# MainBoard.net
KiCad netlist of a schematic drawn in EAGLE
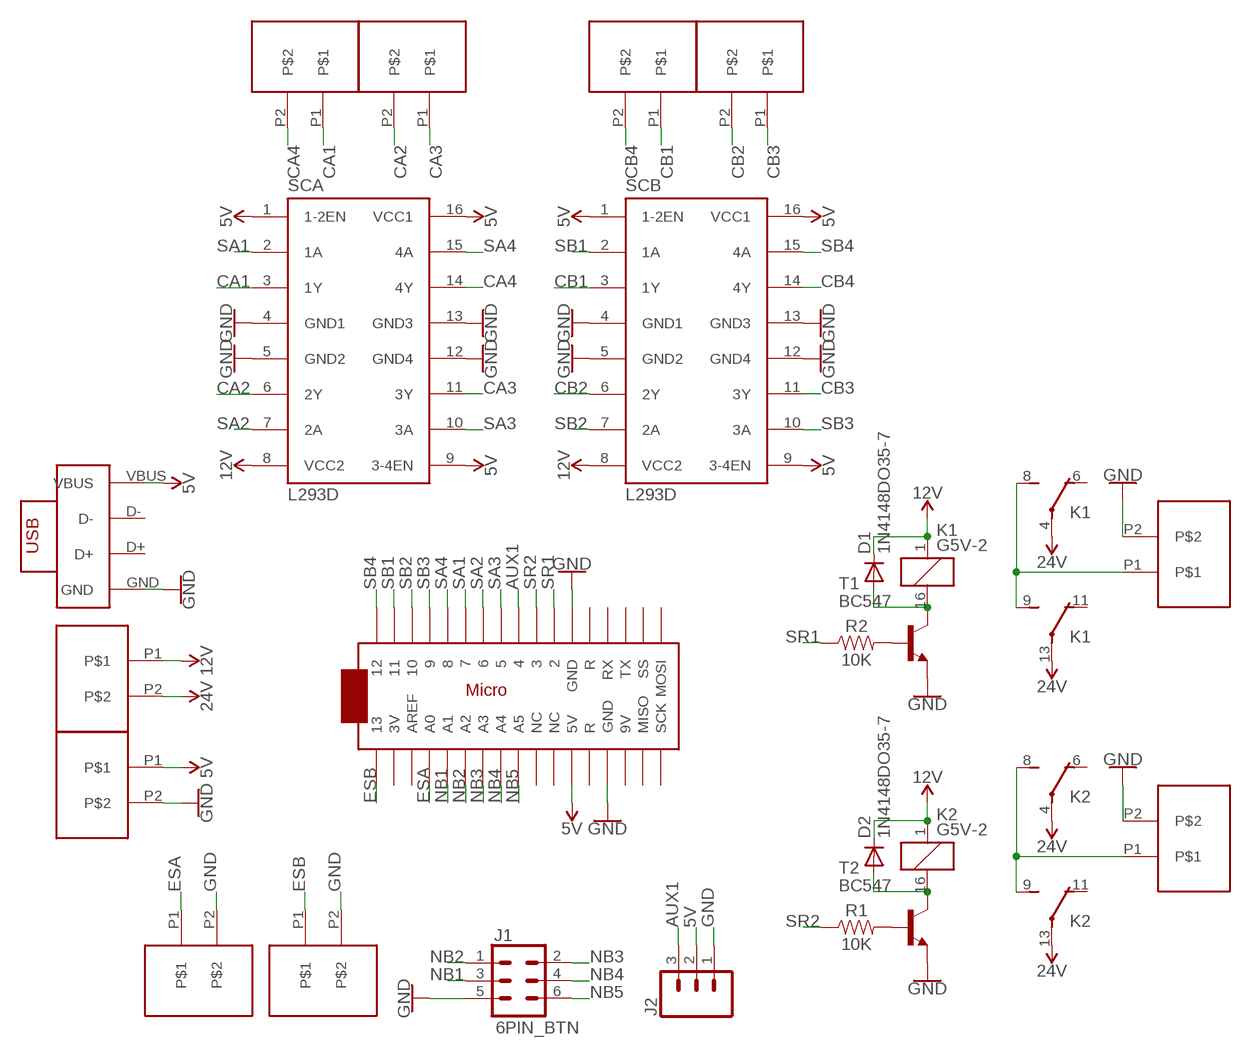
[diagram p0: schematic, sheet 1]

(export (version "E")
  (design (tool "Eeschema 10.0.6"))
  (components
    (comp (ref "5V/GND")
      (value "PRT-08432")
      (footprint "eagle-import:PRT-08432")
      (libsource (lib "eagle-import") (part "PRT-08432"))
    )
    (comp (ref "12/24V")
      (value "PRT-08432")
      (footprint "eagle-import:PRT-08432")
      (libsource (lib "eagle-import") (part "PRT-08432"))
    )
    (comp (ref "D1")
      (value "1N4148DO35-7")
      (footprint "eagle-import:DO35-7")
      (libsource (lib "eagle-import") (part "1N4148DO35-7"))
    )
    (comp (ref "D2")
      (value "1N4148DO35-7")
      (footprint "eagle-import:DO35-7")
      (libsource (lib "eagle-import") (part "1N4148DO35-7"))
    )
    (comp (ref "ESA")
      (value "PRT-08432")
      (footprint "eagle-import:PRT-08432")
      (libsource (lib "eagle-import") (part "PRT-08432"))
    )
    (comp (ref "ESB")
      (value "PRT-08432")
      (footprint "eagle-import:PRT-08432")
      (libsource (lib "eagle-import") (part "PRT-08432"))
    )
    (comp (ref "J1")
      (value "6PIN_BTN")
      (footprint "eagle-import:2X3")
      (libsource (lib "eagle-import") (part "CONN_03X22X3_SILK_MALE_PTH"))
    )
    (comp (ref "J2")
      (value "CONN_03")
      (footprint "eagle-import:1X03")
      (libsource (lib "eagle-import") (part "CONN_03"))
    )
    (comp (ref "K1")
      (value "G5V-2")
      (footprint "eagle-import:G5V-2")
      (fields (field (name "MPN") "G5V-2 5DC"))
      (libsource (lib "eagle-import") (part "G5V-2"))
    )
    (comp (ref "K2")
      (value "G5V-2")
      (footprint "eagle-import:G5V-2")
      (fields (field (name "MPN") "G5V-2 5DC"))
      (libsource (lib "eagle-import") (part "G5V-2"))
    )
    (comp (ref "R1")
      (value "10K")
      (footprint "eagle-import:AXIAL-0.3")
      (libsource (lib "eagle-import") (part "RESISTORAXIAL-0.3"))
    )
    (comp (ref "R2")
      (value "10K")
      (footprint "eagle-import:AXIAL-0.3")
      (libsource (lib "eagle-import") (part "RESISTORAXIAL-0.3"))
    )
    (comp (ref "SCA")
      (value "L293D")
      (footprint "eagle-import:DIL16")
      (libsource (lib "eagle-import") (part "L293D"))
    )
    (comp (ref "SCA12")
      (value "PRT-08432")
      (footprint "eagle-import:PRT-08432")
      (libsource (lib "eagle-import") (part "PRT-08432"))
    )
    (comp (ref "SCA34")
      (value "PRT-08432")
      (footprint "eagle-import:PRT-08432")
      (libsource (lib "eagle-import") (part "PRT-08432"))
    )
    (comp (ref "SCB")
      (value "L293D")
      (footprint "eagle-import:DIL16")
      (libsource (lib "eagle-import") (part "L293D"))
    )
    (comp (ref "SCB12")
      (value "PRT-08432")
      (footprint "eagle-import:PRT-08432")
      (libsource (lib "eagle-import") (part "PRT-08432"))
    )
    (comp (ref "SCB34")
      (value "PRT-08432")
      (footprint "eagle-import:PRT-08432")
      (libsource (lib "eagle-import") (part "PRT-08432"))
    )
    (comp (ref "SR1")
      (value "PRT-08432")
      (footprint "eagle-import:PRT-08432")
      (libsource (lib "eagle-import") (part "PRT-08432"))
    )
    (comp (ref "SR2")
      (value "PRT-08432")
      (footprint "eagle-import:PRT-08432")
      (libsource (lib "eagle-import") (part "PRT-08432"))
    )
    (comp (ref "T1")
      (value "BC547")
      (footprint "eagle-import:TO92")
      (libsource (lib "eagle-import") (part "BC547"))
    )
    (comp (ref "T2")
      (value "BC547")
      (footprint "eagle-import:TO92")
      (libsource (lib "eagle-import") (part "BC547"))
    )
    (comp (ref "U$1")
      (value "ARDUINOMICRO")
      (footprint "eagle-import:ARDUINOMICRO")
      (libsource (lib "eagle-import") (part "ARDUINOMICRO"))
    )
    (comp (ref "U$2")
      (value "USB_EXP_BOARD")
      (footprint "eagle-import:USB_EXPANSION")
      (libsource (lib "eagle-import") (part "USB_EXP_BOARD"))
    )
  )
  (nets
    (net (code "1") (name "/AUX1") (class "Default")
      (node (ref "J2") (pin "3") (pinfunction "3_3") (pintype "passive"))
      (node (ref "U$1") (pin "P$9") (pinfunction "4_P$9") (pintype "bidirectional"))
    )
    (net (code "2") (name "/CA1") (class "Default")
      (node (ref "SCA") (pin "3") (pinfunction "1Y_3") (pintype "output"))
      (node (ref "SCA12") (pin "P1") (pinfunction "P$1_P1") (pintype "bidirectional"))
    )
    (net (code "3") (name "/CA2") (class "Default")
      (node (ref "SCA") (pin "6") (pinfunction "2Y_6") (pintype "output"))
      (node (ref "SCA34") (pin "P2") (pinfunction "P$2_P2") (pintype "bidirectional"))
    )
    (net (code "4") (name "/CA3") (class "Default")
      (node (ref "SCA") (pin "11") (pinfunction "3Y_11") (pintype "output"))
      (node (ref "SCA34") (pin "P1") (pinfunction "P$1_P1") (pintype "bidirectional"))
    )
    (net (code "5") (name "/CA4") (class "Default")
      (node (ref "SCA") (pin "14") (pinfunction "4Y_14") (pintype "output"))
      (node (ref "SCA12") (pin "P2") (pinfunction "P$2_P2") (pintype "bidirectional"))
    )
    (net (code "6") (name "/CB1") (class "Default")
      (node (ref "SCB") (pin "3") (pinfunction "1Y_3") (pintype "output"))
      (node (ref "SCB12") (pin "P1") (pinfunction "P$1_P1") (pintype "bidirectional"))
    )
    (net (code "7") (name "/CB2") (class "Default")
      (node (ref "SCB") (pin "6") (pinfunction "2Y_6") (pintype "output"))
      (node (ref "SCB34") (pin "P2") (pinfunction "P$2_P2") (pintype "bidirectional"))
    )
    (net (code "8") (name "/CB3") (class "Default")
      (node (ref "SCB") (pin "11") (pinfunction "3Y_11") (pintype "output"))
      (node (ref "SCB34") (pin "P1") (pinfunction "P$1_P1") (pintype "bidirectional"))
    )
    (net (code "9") (name "/CB4") (class "Default")
      (node (ref "SCB") (pin "14") (pinfunction "4Y_14") (pintype "output"))
      (node (ref "SCB12") (pin "P2") (pinfunction "P$2_P2") (pintype "bidirectional"))
    )
    (net (code "10") (name "/ESA") (class "Default")
      (node (ref "ESA") (pin "P1") (pinfunction "P$1_P1") (pintype "bidirectional"))
      (node (ref "U$1") (pin "P$31") (pinfunction "A0_P$31") (pintype "bidirectional"))
    )
    (net (code "11") (name "/ESB") (class "Default")
      (node (ref "ESB") (pin "P1") (pinfunction "P$1_P1") (pintype "bidirectional"))
      (node (ref "U$1") (pin "P$34") (pinfunction "13_P$34") (pintype "bidirectional"))
    )
    (net (code "12") (name "/NB1") (class "Default")
      (node (ref "J1") (pin "3") (pinfunction "3_3") (pintype "bidirectional"))
      (node (ref "U$1") (pin "P$30") (pinfunction "A1_P$30") (pintype "bidirectional"))
    )
    (net (code "13") (name "/NB2") (class "Default")
      (node (ref "J1") (pin "1") (pinfunction "1_1") (pintype "bidirectional"))
      (node (ref "U$1") (pin "P$29") (pinfunction "A2_P$29") (pintype "bidirectional"))
    )
    (net (code "14") (name "/NB3") (class "Default")
      (node (ref "J1") (pin "2") (pinfunction "2_2") (pintype "bidirectional"))
      (node (ref "U$1") (pin "P$28") (pinfunction "A3_P$28") (pintype "bidirectional"))
    )
    (net (code "15") (name "/NB4") (class "Default")
      (node (ref "J1") (pin "4") (pinfunction "4_4") (pintype "bidirectional"))
      (node (ref "U$1") (pin "P$27") (pinfunction "A4_P$27") (pintype "bidirectional"))
    )
    (net (code "16") (name "/NB5") (class "Default")
      (node (ref "J1") (pin "6") (pinfunction "6_6") (pintype "bidirectional"))
      (node (ref "U$1") (pin "P$26") (pinfunction "A5_P$26") (pintype "bidirectional"))
    )
    (net (code "17") (name "/SA1") (class "Default")
      (node (ref "SCA") (pin "2") (pinfunction "1A_2") (pintype "input"))
      (node (ref "U$1") (pin "P$6") (pinfunction "7_P$6") (pintype "bidirectional"))
    )
    (net (code "18") (name "/SA2") (class "Default")
      (node (ref "SCA") (pin "7") (pinfunction "2A_7") (pintype "input"))
      (node (ref "U$1") (pin "P$7") (pinfunction "6_P$7") (pintype "bidirectional"))
    )
    (net (code "19") (name "/SA3") (class "Default")
      (node (ref "SCA") (pin "10") (pinfunction "3A_10") (pintype "input"))
      (node (ref "U$1") (pin "P$8") (pinfunction "5_P$8") (pintype "bidirectional"))
    )
    (net (code "20") (name "/SA4") (class "Default")
      (node (ref "SCA") (pin "15") (pinfunction "4A_15") (pintype "input"))
      (node (ref "U$1") (pin "P$5") (pinfunction "8_P$5") (pintype "bidirectional"))
    )
    (net (code "21") (name "/SB1") (class "Default")
      (node (ref "SCB") (pin "2") (pinfunction "1A_2") (pintype "input"))
      (node (ref "U$1") (pin "P$2") (pinfunction "11_P$2") (pintype "bidirectional"))
    )
    (net (code "22") (name "/SB2") (class "Default")
      (node (ref "SCB") (pin "7") (pinfunction "2A_7") (pintype "input"))
      (node (ref "U$1") (pin "P$3") (pinfunction "10_P$3") (pintype "bidirectional"))
    )
    (net (code "23") (name "/SB3") (class "Default")
      (node (ref "SCB") (pin "10") (pinfunction "3A_10") (pintype "input"))
      (node (ref "U$1") (pin "P$4") (pinfunction "9_P$4") (pintype "bidirectional"))
    )
    (net (code "24") (name "/SB4") (class "Default")
      (node (ref "SCB") (pin "15") (pinfunction "4A_15") (pintype "input"))
      (node (ref "U$1") (pin "P$1") (pinfunction "12_P$1") (pintype "bidirectional"))
    )
    (net (code "25") (name "/SR1") (class "Default")
      (node (ref "R2") (pin "P$1") (pinfunction "1_P$1") (pintype "passive"))
      (node (ref "U$1") (pin "P$11") (pinfunction "2_P$11") (pintype "bidirectional"))
    )
    (net (code "26") (name "/SR2") (class "Default")
      (node (ref "R1") (pin "P$1") (pinfunction "1_P$1") (pintype "passive"))
      (node (ref "U$1") (pin "P$10") (pinfunction "3_P$10") (pintype "bidirectional"))
    )
    (net (code "27") (name "5V") (class "Default")
      (node (ref "5V/GND") (pin "P1") (pinfunction "P$1_P1") (pintype "bidirectional"))
      (node (ref "J2") (pin "2") (pinfunction "2_2") (pintype "passive"))
      (node (ref "SCA") (pin "1") (pinfunction "1-2EN_1") (pintype "input"))
      (node (ref "SCA") (pin "16") (pinfunction "VCC1_16") (pintype "power_in"))
      (node (ref "SCA") (pin "9") (pinfunction "3-4EN_9") (pintype "input"))
      (node (ref "SCB") (pin "1") (pinfunction "1-2EN_1") (pintype "input"))
      (node (ref "SCB") (pin "16") (pinfunction "VCC1_16") (pintype "power_in"))
      (node (ref "SCB") (pin "9") (pinfunction "3-4EN_9") (pintype "input"))
      (node (ref "U$1") (pin "P$23") (pinfunction "5V_P$23") (pintype "bidirectional"))
      (node (ref "U$2") (pin "VBUS") (pinfunction "VBUS_VBUS") (pintype "bidirectional"))
    )
    (net (code "28") (name "12V") (class "Default")
      (node (ref "12/24V") (pin "P1") (pinfunction "P$1_P1") (pintype "bidirectional"))
      (node (ref "D1") (pin "C") (pinfunction "C_C") (pintype "passive"))
      (node (ref "D2") (pin "C") (pinfunction "C_C") (pintype "passive"))
      (node (ref "K1") (pin "1") (pinfunction "1_1") (pintype "passive"))
      (node (ref "K2") (pin "1") (pinfunction "1_1") (pintype "passive"))
      (node (ref "SCA") (pin "8") (pinfunction "VCC2_8") (pintype "power_in"))
      (node (ref "SCB") (pin "8") (pinfunction "VCC2_8") (pintype "power_in"))
    )
    (net (code "29") (name "24V") (class "Default")
      (node (ref "12/24V") (pin "P2") (pinfunction "P$2_P2") (pintype "bidirectional"))
      (node (ref "K1") (pin "13") (pinfunction "P_13") (pintype "passive"))
      (node (ref "K1") (pin "4") (pinfunction "P_4") (pintype "passive"))
      (node (ref "K2") (pin "13") (pinfunction "P_13") (pintype "passive"))
      (node (ref "K2") (pin "4") (pinfunction "P_4") (pintype "passive"))
    )
    (net (code "30") (name "GND") (class "Default")
      (node (ref "5V/GND") (pin "P2") (pinfunction "P$2_P2") (pintype "bidirectional"))
      (node (ref "ESA") (pin "P2") (pinfunction "P$2_P2") (pintype "bidirectional"))
      (node (ref "ESB") (pin "P2") (pinfunction "P$2_P2") (pintype "bidirectional"))
      (node (ref "J1") (pin "5") (pinfunction "5_5") (pintype "bidirectional"))
      (node (ref "J2") (pin "1") (pinfunction "1_1") (pintype "passive"))
      (node (ref "SCA") (pin "12") (pinfunction "GND4_12") (pintype "power_in"))
      (node (ref "SCA") (pin "13") (pinfunction "GND3_13") (pintype "power_in"))
      (node (ref "SCA") (pin "4") (pinfunction "GND1_4") (pintype "power_in"))
      (node (ref "SCA") (pin "5") (pinfunction "GND2_5") (pintype "power_in"))
      (node (ref "SCB") (pin "12") (pinfunction "GND4_12") (pintype "power_in"))
      (node (ref "SCB") (pin "13") (pinfunction "GND3_13") (pintype "power_in"))
      (node (ref "SCB") (pin "4") (pinfunction "GND1_4") (pintype "power_in"))
      (node (ref "SCB") (pin "5") (pinfunction "GND2_5") (pintype "power_in"))
      (node (ref "SR1") (pin "P2") (pinfunction "P$2_P2") (pintype "bidirectional"))
      (node (ref "SR2") (pin "P2") (pinfunction "P$2_P2") (pintype "bidirectional"))
      (node (ref "T1") (pin "1") (pinfunction "E_1") (pintype "passive"))
      (node (ref "T2") (pin "1") (pinfunction "E_1") (pintype "passive"))
      (node (ref "U$1") (pin "P$12") (pinfunction "GND_P$12") (pintype "bidirectional"))
      (node (ref "U$1") (pin "P$21") (pinfunction "GND_P$21") (pintype "bidirectional"))
      (node (ref "U$2") (pin "GND") (pinfunction "GND_GND") (pintype "bidirectional"))
    )
    (net (code "31") (name "Net-(K1A-S)") (class "Default")
      (node (ref "K1") (pin "8") (pinfunction "S_8") (pintype "passive"))
      (node (ref "K1") (pin "9") (pinfunction "S_9") (pintype "passive"))
      (node (ref "SR1") (pin "P1") (pinfunction "P$1_P1") (pintype "bidirectional"))
    )
    (net (code "32") (name "Net-(K1C-2)") (class "Default")
      (node (ref "D1") (pin "A") (pinfunction "A_A") (pintype "passive"))
      (node (ref "K1") (pin "16") (pinfunction "2_16") (pintype "passive"))
      (node (ref "T1") (pin "3") (pinfunction "C_3") (pintype "passive"))
    )
    (net (code "33") (name "Net-(K2A-S)") (class "Default")
      (node (ref "K2") (pin "8") (pinfunction "S_8") (pintype "passive"))
      (node (ref "K2") (pin "9") (pinfunction "S_9") (pintype "passive"))
      (node (ref "SR2") (pin "P1") (pinfunction "P$1_P1") (pintype "bidirectional"))
    )
    (net (code "34") (name "Net-(K2C-2)") (class "Default")
      (node (ref "D2") (pin "A") (pinfunction "A_A") (pintype "passive"))
      (node (ref "K2") (pin "16") (pinfunction "2_16") (pintype "passive"))
      (node (ref "T2") (pin "3") (pinfunction "C_3") (pintype "passive"))
    )
    (net (code "35") (name "Net-(R1-2)") (class "Default")
      (node (ref "R1") (pin "P$2") (pinfunction "2_P$2") (pintype "passive"))
      (node (ref "T2") (pin "2") (pinfunction "B_2") (pintype "passive"))
    )
    (net (code "36") (name "Net-(R2-2)") (class "Default")
      (node (ref "R2") (pin "P$2") (pinfunction "2_P$2") (pintype "passive"))
      (node (ref "T1") (pin "2") (pinfunction "B_2") (pintype "passive"))
    )
    (net (code "37") (name "unconnected-(K1A-O-Pad6)") (class "Default")
      (node (ref "K1") (pin "6") (pinfunction "O_6") (pintype "passive"))
    )
    (net (code "38") (name "unconnected-(K1B-O-Pad11)") (class "Default")
      (node (ref "K1") (pin "11") (pinfunction "O_11") (pintype "passive"))
    )
    (net (code "39") (name "unconnected-(K2A-O-Pad6)") (class "Default")
      (node (ref "K2") (pin "6") (pinfunction "O_6") (pintype "passive"))
    )
    (net (code "40") (name "unconnected-(K2B-O-Pad11)") (class "Default")
      (node (ref "K2") (pin "11") (pinfunction "O_11") (pintype "passive"))
    )
    (net (code "41") (name "unconnected-(U$1-3V-PadP$33)") (class "Default")
      (node (ref "U$1") (pin "P$33") (pinfunction "3V_P$33") (pintype "bidirectional"))
    )
    (net (code "42") (name "unconnected-(U$1-9V-PadP$20)") (class "Default")
      (node (ref "U$1") (pin "P$20") (pinfunction "9V_P$20") (pintype "bidirectional"))
    )
    (net (code "43") (name "unconnected-(U$1-AREF-PadP$32)") (class "Default")
      (node (ref "U$1") (pin "P$32") (pinfunction "AREF_P$32") (pintype "bidirectional"))
    )
    (net (code "44") (name "unconnected-(U$1-MISO-PadP$19)") (class "Default")
      (node (ref "U$1") (pin "P$19") (pinfunction "MISO_P$19") (pintype "bidirectional"))
    )
    (net (code "45") (name "unconnected-(U$1-MOSI-PadP$17)") (class "Default")
      (node (ref "U$1") (pin "P$17") (pinfunction "MOSI_P$17") (pintype "bidirectional"))
    )
    (net (code "46") (name "unconnected-(U$1-NC-PadP$24)") (class "Default")
      (node (ref "U$1") (pin "P$24") (pinfunction "NC_P$24") (pintype "bidirectional"))
    )
    (net (code "47") (name "unconnected-(U$1-NC-PadP$25)") (class "Default")
      (node (ref "U$1") (pin "P$25") (pinfunction "NC_P$25") (pintype "bidirectional"))
    )
    (net (code "48") (name "unconnected-(U$1-R-PadP$13)") (class "Default")
      (node (ref "U$1") (pin "P$13") (pinfunction "R_P$13") (pintype "bidirectional"))
    )
    (net (code "49") (name "unconnected-(U$1-R-PadP$22)") (class "Default")
      (node (ref "U$1") (pin "P$22") (pinfunction "R_P$22") (pintype "bidirectional"))
    )
    (net (code "50") (name "unconnected-(U$1-RX-PadP$14)") (class "Default")
      (node (ref "U$1") (pin "P$14") (pinfunction "RX_P$14") (pintype "bidirectional"))
    )
    (net (code "51") (name "unconnected-(U$1-SCK-PadP$18)") (class "Default")
      (node (ref "U$1") (pin "P$18") (pinfunction "SCK_P$18") (pintype "bidirectional"))
    )
    (net (code "52") (name "unconnected-(U$1-SS-PadP$16)") (class "Default")
      (node (ref "U$1") (pin "P$16") (pinfunction "SS_P$16") (pintype "bidirectional"))
    )
    (net (code "53") (name "unconnected-(U$1-TX-PadP$15)") (class "Default")
      (node (ref "U$1") (pin "P$15") (pinfunction "TX_P$15") (pintype "bidirectional"))
    )
    (net (code "54") (name "unconnected-(U$2-PadD+)") (class "Default")
      (node (ref "U$2") (pin "D+") (pinfunction "D+_D+") (pintype "bidirectional"))
    )
    (net (code "55") (name "unconnected-(U$2-PadD-)") (class "Default")
      (node (ref "U$2") (pin "D-") (pinfunction "D-_D-") (pintype "bidirectional"))
    )
  )
)
